# Camera_Board.net
KiCad netlist of a schematic drawn in Altium Designer
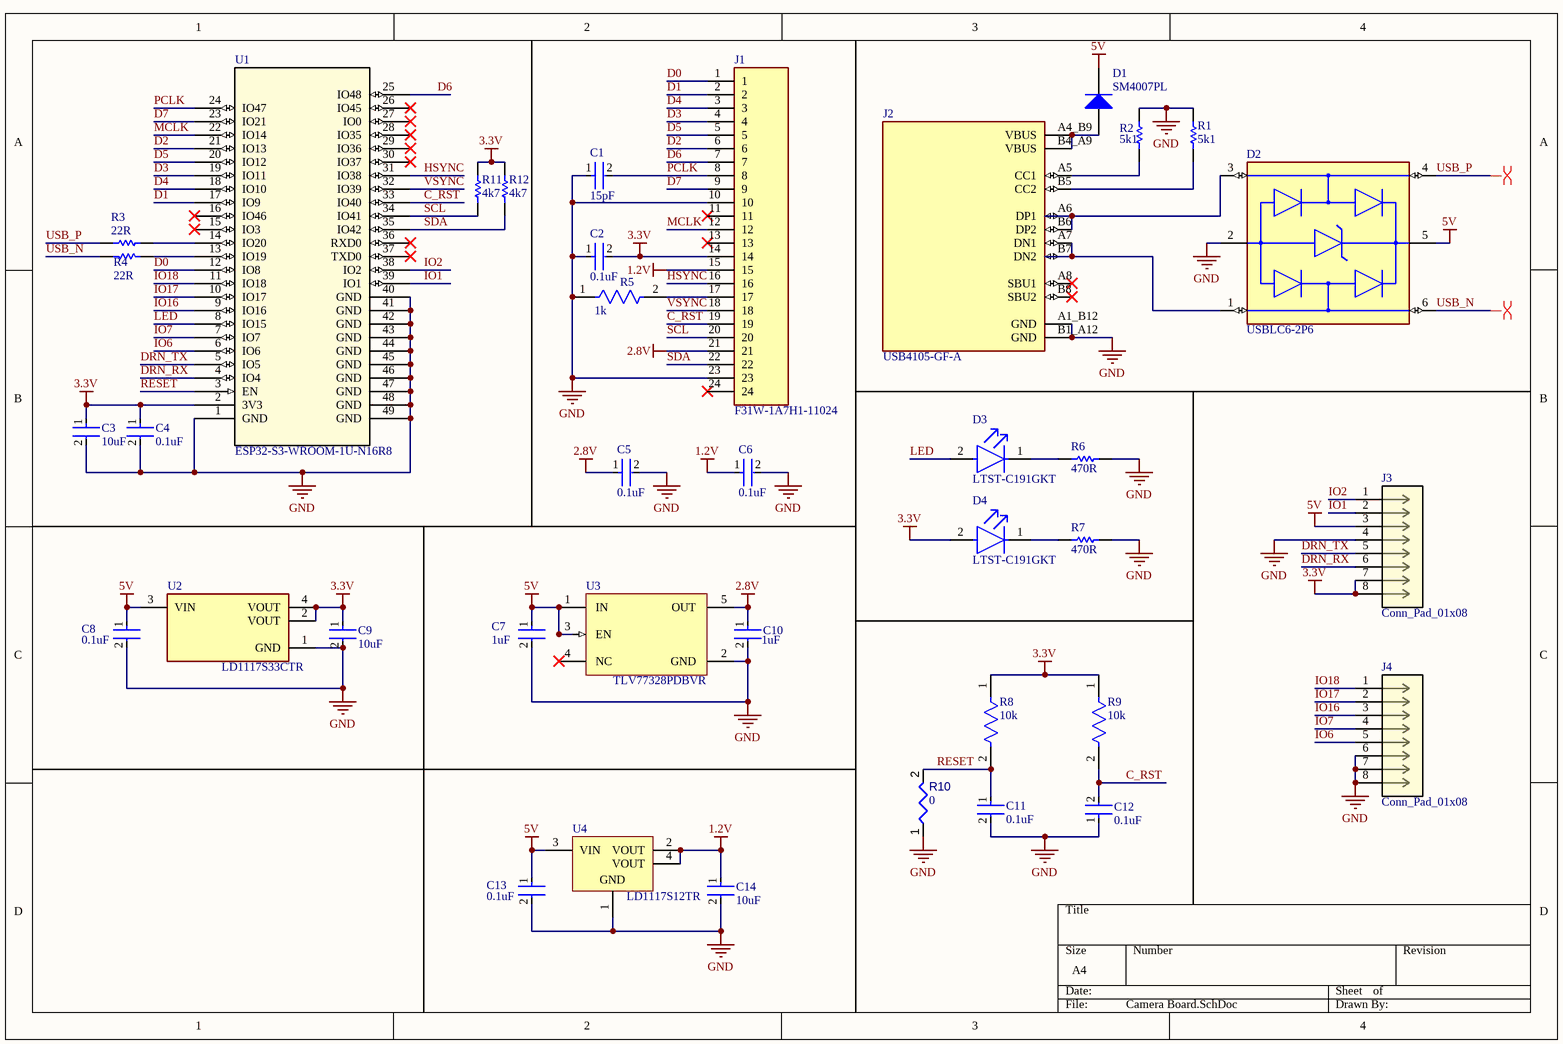
[diagram p0: Camera Board.SchDoc]

(export (version "E")
  (design (tool "Eeschema 10.0.6"))
  (components
    (comp (ref "C1")
      (value "15pF")
      (footprint "FP-CC0402-0_55-IPC_B")
      (description "CAP CER 15PF 50V C0G/NPO 0402")
      (fields (field (name "VOLTAGE") "50V") (field (name "TOLERANCE") "5%"))
      (libsource (lib "Altium Content Vault") (part "b4654b650e69147ec39a6b967a45e02"))
    )
    (comp (ref "C2")
      (value "0.1uF")
      (footprint "FP-GRM155-0_05-IPC_B")
      (description "Chip Multilayer Ceramic Capacitors for General Purpose, 0402, 0.10uF, X7R, 15%, 10%, 50V")
      (fields (field (name "VOLTAGE") "50V") (field (name "TOLERANCE") "10%"))
      (libsource (lib "Altium Content Vault") (part "02cd4be3c70576c341d710602a673aa"))
    )
    (comp (ref "C3")
      (value "10uF")
      (footprint "FP-GRM18-0_15-MFG")
      (description "CAP CER 10UF 10V X5R 0603")
      (fields
        (field (name "OCTOPART") "https://octopart.com/grm188r61a106ke69d-murata-22851381")
        (field (name "MANUFACTURER PART NUMBER") "GRM188R61A106KE69D")
      )
      (libsource (lib "Altium Content Vault") (part "11868f565c42a9108669ba33697ecf6"))
    )
    (comp (ref "C4")
      (value "0.1uF")
      (footprint "FP-CC0603-DA-MFG")
      (description "CAP CER 0.1UF 50V X7R 0603")
      (fields (field (name "MANUFACTURER") "YAGEO") (field (name "VOLTAGE") "50 V"))
      (libsource (lib "Altium Content Vault") (part "11868f565c42a9108669ba33697ecf6"))
    )
    (comp (ref "C5")
      (value "0.1uF")
      (footprint "FP-GRM155-0_05-IPC_B")
      (description "Chip Multilayer Ceramic Capacitors for General Purpose, 0402, 0.10uF, X7R, 15%, 10%, 50V")
      (fields (field (name "VOLTAGE") "50V") (field (name "TOLERANCE") "10%"))
      (libsource (lib "Altium Content Vault") (part "02cd4be3c70576c341d710602a673aa"))
    )
    (comp (ref "C6")
      (value "0.1uF")
      (footprint "FP-GRM155-0_05-IPC_B")
      (description "Chip Multilayer Ceramic Capacitors for General Purpose, 0402, 0.10uF, X7R, 15%, 10%, 50V")
      (fields (field (name "VOLTAGE") "50V") (field (name "TOLERANCE") "10%"))
      (libsource (lib "Altium Content Vault") (part "02cd4be3c70576c341d710602a673aa"))
    )
    (comp (ref "C7")
      (value "1uF")
      (footprint "FP-CC0603-DB-MFG")
      (description "CAP CER 1UF 50V X7R 0603")
      (fields (field (name "TOLERANCE") "10%"))
      (libsource (lib "Altium Content Vault") (part "11868f565c42a9108669ba33697ecf6"))
    )
    (comp (ref "C8")
      (value "0.1uF")
      (footprint "FP-CC0603-DA-MFG")
      (description "CAP CER 0.1UF 50V X7R 0603")
      (fields (field (name "MANUFACTURER") "YAGEO") (field (name "VOLTAGE") "50 V"))
      (libsource (lib "Altium Content Vault") (part "11868f565c42a9108669ba33697ecf6"))
    )
    (comp (ref "C9")
      (value "10uF")
      (footprint "FP-GRM18-0_15-MFG")
      (description "CAP CER 10UF 10V X5R 0603")
      (fields
        (field (name "OCTOPART") "https://octopart.com/grm188r61a106ke69d-murata-22851381")
        (field (name "MANUFACTURER PART NUMBER") "GRM188R61A106KE69D")
      )
      (libsource (lib "Altium Content Vault") (part "11868f565c42a9108669ba33697ecf6"))
    )
    (comp (ref "C10")
      (value "1uF")
      (footprint "FP-CC0603-DB-MFG")
      (description "CAP CER 1UF 50V X7R 0603")
      (fields (field (name "TOLERANCE") "10%"))
      (libsource (lib "Altium Content Vault") (part "11868f565c42a9108669ba33697ecf6"))
    )
    (comp (ref "C11")
      (value "0.1uF")
      (footprint "FP-CC0603-DA-MFG")
      (description "CAP CER 0.1UF 50V X7R 0603")
      (fields (field (name "MANUFACTURER") "YAGEO") (field (name "VOLTAGE") "50 V"))
      (libsource (lib "Altium Content Vault") (part "11868f565c42a9108669ba33697ecf6"))
    )
    (comp (ref "C12")
      (value "0.1uF")
      (footprint "FP-GRM155-0_05-IPC_B")
      (description "Chip Multilayer Ceramic Capacitors for General Purpose, 0402, 0.10uF, X7R, 15%, 10%, 50V")
      (fields (field (name "VOLTAGE") "50V") (field (name "TOLERANCE") "10%"))
      (libsource (lib "Altium Content Vault") (part "02cd4be3c70576c341d710602a673aa"))
    )
    (comp (ref "C13")
      (value "0.1uF")
      (footprint "FP-CC0603-DA-MFG")
      (description "CAP CER 0.1UF 50V X7R 0603")
      (fields (field (name "MANUFACTURER") "YAGEO") (field (name "VOLTAGE") "50 V"))
      (libsource (lib "Altium Content Vault") (part "11868f565c42a9108669ba33697ecf6"))
    )
    (comp (ref "C14")
      (value "10uF")
      (footprint "FP-GRM18-0_15-MFG")
      (description "CAP CER 10UF 10V X5R 0603")
      (fields
        (field (name "OCTOPART") "https://octopart.com/grm188r61a106ke69d-murata-22851381")
        (field (name "MANUFACTURER PART NUMBER") "GRM188R61A106KE69D")
      )
      (libsource (lib "Altium Content Vault") (part "11868f565c42a9108669ba33697ecf6"))
    )
    (comp (ref "D1")
      (value "SM4007PL")
      (footprint "MCC-SOD-123FL_V")
      (description "Silion Rectifier, 1 A, 1000 V, -65 to 175 degC, 2-Pin SMD, RoHS, Tape and Reel")
      (fields (field (name "MANUFACTURER") "Micro Commercial Components"))
      (libsource (lib "Altium Content Vault") (part "D-AK-2"))
    )
    (comp (ref "D2")
      (value "USBLC6-2P6")
      (footprint "FP-SOT-666-MFG")
      (description "TVS DIODE 5.25V 17V SOT666")
      (libsource (lib "Altium Content Vault") (part "c871e55f7e3243d341edbd671b98d92"))
    )
    (comp (ref "D3")
      (value "LTST-C191GKT")
      (footprint "FP-LTST-C191GKT-MFG")
      (description "LED GREEN CLEAR CHIP SMD")
      (libsource (lib "Altium Content Vault") (part "8706943c75ba83719d021d2fdc84c58"))
    )
    (comp (ref "D4")
      (value "LTST-C191GKT")
      (footprint "FP-LTST-C191GKT-MFG")
      (description "LED GREEN CLEAR CHIP SMD")
      (libsource (lib "Altium Content Vault") (part "8706943c75ba83719d021d2fdc84c58"))
    )
    (comp (ref "J1")
      (value "F31W-1A7H1-11024")
      (footprint "AMPHENOL_F31W-1A7H1-11024")
      (fields (field (name "MF") "Amphenol ICC / Aorora"))
      (libsource (lib "Adam Turaj") (part "F31W-1A7H1-11024"))
    )
    (comp (ref "J2")
      (value "USB4105-GF-A")
      (footprint "GCT_USB4105-GF-A")
      (fields (field (name "MF") "{'manufacturer': u'GCT'}"))
      (libsource (lib "Adam Turaj") (part "USB4105-GF-A"))
    )
    (comp (ref "J3")
      (value "Conn_Pad_01x08")
      (footprint "CONN_SM08B-GHS-TB_JST")
      (description "Description")
      (fields (field (name "COPYRIGHT") "Copyright (C) 2026 Ultra Librarian. All rights reserved."))
      (libsource (lib "Adam Turaj") (part "SM08B-GHS-TB"))
    )
    (comp (ref "J4")
      (value "Conn_Pad_01x08")
      (footprint "CONN_SM08B-GHS-TB_JST")
      (description "Description")
      (fields (field (name "COPYRIGHT") "Copyright (C) 2026 Ultra Librarian. All rights reserved."))
      (libsource (lib "Adam Turaj") (part "SM08B-GHS-TB"))
    )
    (comp (ref "R1")
      (value "5k1")
      (footprint "RESC1608X55X25ML10T15")
      (fields (field (name "MANUFACTURER") "Yageo") (field (name "PART NUMBER") "RC0603FR-075K1L"))
      (libsource (lib "Altium Content Vault") (part "RES"))
    )
    (comp (ref "R2")
      (value "5k1")
      (footprint "RESC1608X55X25ML10T15")
      (fields (field (name "MANUFACTURER") "Yageo") (field (name "PART NUMBER") "RC0603FR-075K1L"))
      (libsource (lib "Altium Content Vault") (part "RES"))
    )
    (comp (ref "R3")
      (value "22R")
      (footprint "RESC1608X55X25NL10T15")
      (description "Chip Resistor, 22 Ohm, +/- 1%, 0.1 W, -55 to 155 degC, 0603 (1608 Metric), RoHS, Tape and Reel")
      (libsource (lib "Altium Content Vault") (part "RES-2"))
    )
    (comp (ref "R4")
      (value "22R")
      (footprint "RESC1608X55X25NL10T15")
      (description "Chip Resistor, 22 Ohm, +/- 1%, 0.1 W, -55 to 155 degC, 0603 (1608 Metric), RoHS, Tape and Reel")
      (libsource (lib "Altium Content Vault") (part "RES-2"))
    )
    (comp (ref "R5")
      (value "1k")
      (footprint "FP-RC0603-0_55-IPC_C")
      (description "RES 1K OHM 1% 1/10W 0603")
      (fields (field (name "TOLERANCE") "1%"))
      (libsource (lib "Altium Content Vault") (part "1029c3af85768c4190bb7ad29bc67b5"))
    )
    (comp (ref "R6")
      (value "470R")
      (footprint "RESC1608X55X25LL10T15")
      (libsource (lib "Altium Content Vault") (part "RES-2"))
    )
    (comp (ref "R7")
      (value "470R")
      (footprint "RESC1608X55X25LL10T15")
      (libsource (lib "Altium Content Vault") (part "RES-2"))
    )
    (comp (ref "R8")
      (value "10k")
      (footprint "FP-RC0603-0_55-IPC_C")
      (description "RES 10K OHM 1% 1/10W 0603")
      (fields (field (name "TOLERANCE") "1%"))
      (libsource (lib "Altium Content Vault") (part "1029c3af85768c4190bb7ad29bc67b5"))
    )
    (comp (ref "R9")
      (value "10k")
      (footprint "FP-RC0603-0_55-IPC_C")
      (description "RES 10K OHM 1% 1/10W 0603")
      (fields (field (name "TOLERANCE") "1%"))
      (libsource (lib "Altium Content Vault") (part "1029c3af85768c4190bb7ad29bc67b5"))
    )
    (comp (ref "R10")
      (value "0")
      (footprint "RESC0603(1608)_L")
      (description "Jumper 0603")
      (libsource (lib "UWFE_2025_designs") (part "RES-2"))
    )
    (comp (ref "R11")
      (value "4k7")
      (footprint "RESC1608X55X25LL10T15")
      (description "Chip Resistor, 4.7 KOhm, +/- 1%, 0.1 W, -55 to 155 degC, 0603 (1608 Metric), RoHS, Tape and Reel")
      (fields (field (name "MANUFACTURER") "Yageo") (field (name "TOLERANCE") "1%"))
      (libsource (lib "Altium Content Vault") (part "RES-2"))
    )
    (comp (ref "R12")
      (value "4k7")
      (footprint "RESC1608X55X25LL10T15")
      (description "Chip Resistor, 4.7 KOhm, +/- 1%, 0.1 W, -55 to 155 degC, 0603 (1608 Metric), RoHS, Tape and Reel")
      (fields (field (name "MANUFACTURER") "Yageo") (field (name "TOLERANCE") "1%"))
      (libsource (lib "Altium Content Vault") (part "RES-2"))
    )
    (comp (ref "U1")
      (value "ESP32-S3-WROOM-1U-N16R8")
      (footprint "ESP32-S3-WROOM-1U_EXP")
      (description "Description")
      (fields (field (name "COPYRIGHT") "Copyright (C) 2025 Ultra Librarian. All rights reserved."))
      (libsource (lib "UWFE_2025_designs") (part "ESP32-S3-WROOM-1U-N16R8"))
    )
    (comp (ref "U2")
      (value "LD1117S33CTR")
      (footprint "FP-SOT-223-0046067_14-MFG")
      (description "IC REG LINEAR 3.3V 800MA SOT223")
      (libsource (lib "Altium Content Vault") (part "7818869c5c16ceab15634627166a29d"))
    )
    (comp (ref "U3")
      (value "TLV77328PDBVR")
      (footprint "DBV0005A_MFG")
      (description "300-mA high-PSRR low-IQ low-dropout regulator with enable 5-SOT-23 -40 to 85")
      (libsource (lib "Altium Content Vault") (part "e913c5229f21c84fcd86506975bf48d"))
    )
    (comp (ref "U4")
      (value "LD1117S12TR")
      (footprint "SOT-223_M")
      (description "Fixed Low Drop Positive Voltage Regulator, 1.2V, 4-Pin SOT-223, Tape and Reel")
      (libsource (lib "Altium Content Vault") (part "PM-REG-LD1117-SOT4"))
    )
  )
  (nets
    (net (code "1") (name "/C_RST") (class "Default")
      (node (ref "C12") (pin "2") (pinfunction "2_2") (pintype "passive"))
      (node (ref "J1") (pin "19") (pinfunction "19_19") (pintype "passive"))
      (node (ref "R9") (pin "2") (pinfunction "2_2") (pintype "passive"))
      (node (ref "U1") (pin "33") (pinfunction "IO40_33") (pintype "bidirectional"))
    )
    (net (code "2") (name "/D0") (class "Default")
      (node (ref "J1") (pin "1") (pinfunction "1_1") (pintype "passive"))
      (node (ref "U1") (pin "12") (pinfunction "IO8_12") (pintype "bidirectional"))
    )
    (net (code "3") (name "/D1") (class "Default")
      (node (ref "J1") (pin "2") (pinfunction "2_2") (pintype "passive"))
      (node (ref "U1") (pin "17") (pinfunction "IO9_17") (pintype "bidirectional"))
    )
    (net (code "4") (name "/D2") (class "Default")
      (node (ref "J1") (pin "6") (pinfunction "6_6") (pintype "passive"))
      (node (ref "U1") (pin "21") (pinfunction "IO13_21") (pintype "bidirectional"))
    )
    (net (code "5") (name "/D3") (class "Default")
      (node (ref "J1") (pin "4") (pinfunction "4_4") (pintype "passive"))
      (node (ref "U1") (pin "19") (pinfunction "IO11_19") (pintype "bidirectional"))
    )
    (net (code "6") (name "/D4") (class "Default")
      (node (ref "J1") (pin "3") (pinfunction "3_3") (pintype "passive"))
      (node (ref "U1") (pin "18") (pinfunction "IO10_18") (pintype "bidirectional"))
    )
    (net (code "7") (name "/D5") (class "Default")
      (node (ref "J1") (pin "5") (pinfunction "5_5") (pintype "passive"))
      (node (ref "U1") (pin "20") (pinfunction "IO12_20") (pintype "bidirectional"))
    )
    (net (code "8") (name "/D6") (class "Default")
      (node (ref "J1") (pin "7") (pinfunction "7_7") (pintype "passive"))
      (node (ref "U1") (pin "25") (pinfunction "IO48_25") (pintype "bidirectional"))
    )
    (net (code "9") (name "/D7") (class "Default")
      (node (ref "J1") (pin "9") (pinfunction "9_9") (pintype "passive"))
      (node (ref "U1") (pin "23") (pinfunction "IO21_23") (pintype "bidirectional"))
    )
    (net (code "10") (name "/DRN_RX") (class "Default")
      (node (ref "J3") (pin "6") (pinfunction "6_6") (pintype "passive"))
      (node (ref "U1") (pin "4") (pinfunction "IO4_4") (pintype "bidirectional"))
    )
    (net (code "11") (name "/DRN_TX") (class "Default")
      (node (ref "J3") (pin "5") (pinfunction "5_5") (pintype "passive"))
      (node (ref "U1") (pin "5") (pinfunction "IO5_5") (pintype "bidirectional"))
    )
    (net (code "12") (name "/HSYNC") (class "Default")
      (node (ref "J1") (pin "16") (pinfunction "16_16") (pintype "passive"))
      (node (ref "U1") (pin "31") (pinfunction "IO38_31") (pintype "bidirectional"))
    )
    (net (code "13") (name "/IO1") (class "Default")
      (node (ref "J3") (pin "2") (pinfunction "2_2") (pintype "passive"))
      (node (ref "U1") (pin "39") (pinfunction "IO1_39") (pintype "bidirectional"))
    )
    (net (code "14") (name "/IO2") (class "Default")
      (node (ref "J3") (pin "1") (pinfunction "1_1") (pintype "passive"))
      (node (ref "U1") (pin "38") (pinfunction "IO2_38") (pintype "bidirectional"))
    )
    (net (code "15") (name "/IO6") (class "Default")
      (node (ref "J4") (pin "5") (pinfunction "5_5") (pintype "passive"))
      (node (ref "U1") (pin "6") (pinfunction "IO6_6") (pintype "bidirectional"))
    )
    (net (code "16") (name "/IO7") (class "Default")
      (node (ref "J4") (pin "4") (pinfunction "4_4") (pintype "passive"))
      (node (ref "U1") (pin "7") (pinfunction "IO7_7") (pintype "bidirectional"))
    )
    (net (code "17") (name "/IO16") (class "Default")
      (node (ref "J4") (pin "3") (pinfunction "3_3") (pintype "passive"))
      (node (ref "U1") (pin "9") (pinfunction "IO16_9") (pintype "bidirectional"))
    )
    (net (code "18") (name "/IO17") (class "Default")
      (node (ref "J4") (pin "2") (pinfunction "2_2") (pintype "passive"))
      (node (ref "U1") (pin "10") (pinfunction "IO17_10") (pintype "bidirectional"))
    )
    (net (code "19") (name "/IO18") (class "Default")
      (node (ref "J4") (pin "1") (pinfunction "1_1") (pintype "passive"))
      (node (ref "U1") (pin "11") (pinfunction "IO18_11") (pintype "bidirectional"))
    )
    (net (code "20") (name "/LED") (class "Default")
      (node (ref "D3") (pin "2") (pinfunction "A_2") (pintype "passive"))
      (node (ref "U1") (pin "8") (pinfunction "IO15_8") (pintype "bidirectional"))
    )
    (net (code "21") (name "/MCLK") (class "Default")
      (node (ref "J1") (pin "12") (pinfunction "12_12") (pintype "passive"))
      (node (ref "U1") (pin "22") (pinfunction "IO14_22") (pintype "bidirectional"))
    )
    (net (code "22") (name "/PCLK") (class "Default")
      (node (ref "C1") (pin "2") (pinfunction "2_2") (pintype "passive"))
      (node (ref "J1") (pin "8") (pinfunction "8_8") (pintype "passive"))
      (node (ref "U1") (pin "24") (pinfunction "IO47_24") (pintype "bidirectional"))
    )
    (net (code "23") (name "/RESET") (class "Default")
      (node (ref "C11") (pin "1") (pinfunction "1_1") (pintype "passive"))
      (node (ref "R10") (pin "2") (pinfunction "2_2") (pintype "passive"))
      (node (ref "R8") (pin "2") (pinfunction "2_2") (pintype "passive"))
      (node (ref "U1") (pin "3") (pinfunction "EN_3") (pintype "input"))
    )
    (net (code "24") (name "/SCL") (class "Default")
      (node (ref "J1") (pin "20") (pinfunction "20_20") (pintype "passive"))
      (node (ref "R11") (pin "1") (pinfunction "1_1") (pintype "passive"))
      (node (ref "U1") (pin "34") (pinfunction "IO41_34") (pintype "bidirectional"))
    )
    (net (code "25") (name "/SDA") (class "Default")
      (node (ref "J1") (pin "22") (pinfunction "22_22") (pintype "passive"))
      (node (ref "R12") (pin "1") (pinfunction "1_1") (pintype "passive"))
      (node (ref "U1") (pin "35") (pinfunction "IO42_35") (pintype "bidirectional"))
    )
    (net (code "26") (name "/USB_N") (class "Default")
      (node (ref "D2") (pin "6") (pinfunction "I/O1_6") (pintype "bidirectional"))
      (node (ref "R4") (pin "1") (pinfunction "1_1") (pintype "passive"))
    )
    (net (code "27") (name "/USB_P") (class "Default")
      (node (ref "D2") (pin "4") (pinfunction "I/O2_4") (pintype "bidirectional"))
      (node (ref "R3") (pin "1") (pinfunction "1_1") (pintype "passive"))
    )
    (net (code "28") (name "/VSYNC") (class "Default")
      (node (ref "J1") (pin "18") (pinfunction "18_18") (pintype "passive"))
      (node (ref "U1") (pin "32") (pinfunction "IO39_32") (pintype "bidirectional"))
    )
    (net (code "29") (name "1.2V") (class "Default")
      (node (ref "C14") (pin "1") (pinfunction "1_1") (pintype "passive"))
      (node (ref "C6") (pin "1") (pinfunction "1_1") (pintype "passive"))
      (node (ref "J1") (pin "15") (pinfunction "15_15") (pintype "passive"))
      (node (ref "U4") (pin "2") (pinfunction "VOUT_2") (pintype "power_in"))
      (node (ref "U4") (pin "4") (pinfunction "VOUT_4") (pintype "power_in"))
    )
    (net (code "30") (name "2.8V") (class "Default")
      (node (ref "C10") (pin "1") (pinfunction "1_1") (pintype "passive"))
      (node (ref "C5") (pin "1") (pinfunction "1_1") (pintype "passive"))
      (node (ref "J1") (pin "21") (pinfunction "21_21") (pintype "passive"))
      (node (ref "U3") (pin "5") (pinfunction "OUT_5") (pintype "passive"))
    )
    (net (code "31") (name "3.3V") (class "Default")
      (node (ref "C2") (pin "2") (pinfunction "2_2") (pintype "passive"))
      (node (ref "C3") (pin "1") (pinfunction "1_1") (pintype "passive"))
      (node (ref "C4") (pin "1") (pinfunction "1_1") (pintype "passive"))
      (node (ref "C9") (pin "1") (pinfunction "1_1") (pintype "passive"))
      (node (ref "D4") (pin "2") (pinfunction "A_2") (pintype "passive"))
      (node (ref "J1") (pin "14") (pinfunction "14_14") (pintype "passive"))
      (node (ref "J3") (pin "7") (pinfunction "7_7") (pintype "passive"))
      (node (ref "J3") (pin "8") (pinfunction "8_8") (pintype "passive"))
      (node (ref "R11") (pin "2") (pinfunction "2_2") (pintype "passive"))
      (node (ref "R12") (pin "2") (pinfunction "2_2") (pintype "passive"))
      (node (ref "R8") (pin "1") (pinfunction "1_1") (pintype "passive"))
      (node (ref "R9") (pin "1") (pinfunction "1_1") (pintype "passive"))
      (node (ref "U1") (pin "2") (pinfunction "3V3_2") (pintype "power_in"))
      (node (ref "U2") (pin "2") (pinfunction "VOUT_2") (pintype "power_in"))
      (node (ref "U2") (pin "4") (pinfunction "VOUT_4") (pintype "power_in"))
    )
    (net (code "32") (name "5V") (class "Default")
      (node (ref "C13") (pin "1") (pinfunction "1_1") (pintype "passive"))
      (node (ref "C7") (pin "1") (pinfunction "1_1") (pintype "passive"))
      (node (ref "C8") (pin "1") (pinfunction "1_1") (pintype "passive"))
      (node (ref "D1") (pin "2") (pinfunction "K_2") (pintype "passive"))
      (node (ref "D2") (pin "5") (pinfunction "VBUS_5") (pintype "power_in"))
      (node (ref "J3") (pin "3") (pinfunction "3_3") (pintype "passive"))
      (node (ref "U2") (pin "3") (pinfunction "VIN_3") (pintype "power_in"))
      (node (ref "U3") (pin "1") (pinfunction "IN_1") (pintype "power_in"))
      (node (ref "U3") (pin "3") (pinfunction "EN_3") (pintype "input"))
      (node (ref "U4") (pin "3") (pinfunction "VIN_3") (pintype "power_in"))
    )
    (net (code "33") (name "GND") (class "Default")
      (node (ref "C1") (pin "1") (pinfunction "1_1") (pintype "passive"))
      (node (ref "C10") (pin "2") (pinfunction "2_2") (pintype "passive"))
      (node (ref "C11") (pin "2") (pinfunction "2_2") (pintype "passive"))
      (node (ref "C12") (pin "1") (pinfunction "1_1") (pintype "passive"))
      (node (ref "C13") (pin "2") (pinfunction "2_2") (pintype "passive"))
      (node (ref "C14") (pin "2") (pinfunction "2_2") (pintype "passive"))
      (node (ref "C2") (pin "1") (pinfunction "1_1") (pintype "passive"))
      (node (ref "C3") (pin "2") (pinfunction "2_2") (pintype "passive"))
      (node (ref "C4") (pin "2") (pinfunction "2_2") (pintype "passive"))
      (node (ref "C5") (pin "2") (pinfunction "2_2") (pintype "passive"))
      (node (ref "C6") (pin "2") (pinfunction "2_2") (pintype "passive"))
      (node (ref "C7") (pin "2") (pinfunction "2_2") (pintype "passive"))
      (node (ref "C8") (pin "2") (pinfunction "2_2") (pintype "passive"))
      (node (ref "C9") (pin "2") (pinfunction "2_2") (pintype "passive"))
      (node (ref "D2") (pin "2") (pinfunction "GND_2") (pintype "power_in"))
      (node (ref "J1") (pin "10") (pinfunction "10_10") (pintype "passive"))
      (node (ref "J1") (pin "23") (pinfunction "23_23") (pintype "passive"))
      (node (ref "J2") (pin "A1_B12") (pinfunction "GND_A1_B12") (pintype "power_in"))
      (node (ref "J2") (pin "B1_A12") (pinfunction "GND_B1_A12") (pintype "power_in"))
      (node (ref "J3") (pin "4") (pinfunction "4_4") (pintype "passive"))
      (node (ref "J4") (pin "6") (pinfunction "6_6") (pintype "passive"))
      (node (ref "J4") (pin "7") (pinfunction "7_7") (pintype "passive"))
      (node (ref "J4") (pin "8") (pinfunction "8_8") (pintype "passive"))
      (node (ref "R1") (pin "2") (pinfunction "2_2") (pintype "passive"))
      (node (ref "R10") (pin "1") (pinfunction "1_1") (pintype "passive"))
      (node (ref "R2") (pin "2") (pinfunction "2_2") (pintype "passive"))
      (node (ref "R5") (pin "1") (pinfunction "1_1") (pintype "passive"))
      (node (ref "R6") (pin "2") (pinfunction "2_2") (pintype "passive"))
      (node (ref "R7") (pin "2") (pinfunction "2_2") (pintype "passive"))
      (node (ref "U1") (pin "1") (pinfunction "GND_1") (pintype "power_in"))
      (node (ref "U1") (pin "40") (pinfunction "GND_40") (pintype "power_in"))
      (node (ref "U1") (pin "41") (pinfunction "GND_41") (pintype "power_in"))
      (node (ref "U1") (pin "42") (pinfunction "GND_42") (pintype "power_in"))
      (node (ref "U1") (pin "43") (pinfunction "GND_43") (pintype "power_in"))
      (node (ref "U1") (pin "44") (pinfunction "GND_44") (pintype "power_in"))
      (node (ref "U1") (pin "45") (pinfunction "GND_45") (pintype "power_in"))
      (node (ref "U1") (pin "46") (pinfunction "GND_46") (pintype "power_in"))
      (node (ref "U1") (pin "47") (pinfunction "GND_47") (pintype "power_in"))
      (node (ref "U1") (pin "48") (pinfunction "GND_48") (pintype "power_in"))
      (node (ref "U1") (pin "49") (pinfunction "GND_49") (pintype "power_in"))
      (node (ref "U2") (pin "1") (pinfunction "GND_1") (pintype "power_in"))
      (node (ref "U3") (pin "2") (pinfunction "GND_2") (pintype "power_in"))
      (node (ref "U4") (pin "1") (pinfunction "GND_1") (pintype "power_in"))
    )
    (net (code "34") (name "Net-(D1-A)") (class "Default")
      (node (ref "D1") (pin "1") (pinfunction "A_1") (pintype "passive"))
      (node (ref "J2") (pin "A4_B9") (pinfunction "VBUS_A4_B9") (pintype "power_in"))
      (node (ref "J2") (pin "B4_A9") (pinfunction "VBUS_B4_A9") (pintype "power_in"))
    )
    (net (code "35") (name "Net-(D3-C)") (class "Default")
      (node (ref "D3") (pin "1") (pinfunction "C_1") (pintype "passive"))
      (node (ref "R6") (pin "1") (pinfunction "1_1") (pintype "passive"))
    )
    (net (code "36") (name "Net-(D4-C)") (class "Default")
      (node (ref "D4") (pin "1") (pinfunction "C_1") (pintype "passive"))
      (node (ref "R7") (pin "1") (pinfunction "1_1") (pintype "passive"))
    )
    (net (code "37") (name "Net-(J1-Pad17)") (class "Default")
      (node (ref "J1") (pin "17") (pinfunction "17_17") (pintype "passive"))
      (node (ref "R5") (pin "2") (pinfunction "2_2") (pintype "passive"))
    )
    (net (code "38") (name "Net-(J2-CC1)") (class "Default")
      (node (ref "J2") (pin "A5") (pinfunction "CC1_A5") (pintype "bidirectional"))
      (node (ref "R2") (pin "1") (pinfunction "1_1") (pintype "passive"))
    )
    (net (code "39") (name "Net-(J2-CC2)") (class "Default")
      (node (ref "J2") (pin "B5") (pinfunction "CC2_B5") (pintype "bidirectional"))
      (node (ref "R1") (pin "1") (pinfunction "1_1") (pintype "passive"))
    )
    (net (code "40") (name "Net-(J2-DN1)") (class "Default")
      (node (ref "D2") (pin "1") (pinfunction "I/O1_1") (pintype "bidirectional"))
      (node (ref "J2") (pin "A7") (pinfunction "DN1_A7") (pintype "bidirectional"))
      (node (ref "J2") (pin "B7") (pinfunction "DN2_B7") (pintype "bidirectional"))
    )
    (net (code "41") (name "Net-(J2-DP1)") (class "Default")
      (node (ref "D2") (pin "3") (pinfunction "I/O2_3") (pintype "bidirectional"))
      (node (ref "J2") (pin "A6") (pinfunction "DP1_A6") (pintype "bidirectional"))
      (node (ref "J2") (pin "B6") (pinfunction "DP2_B6") (pintype "bidirectional"))
    )
    (net (code "42") (name "Net-(U1-IO19)") (class "Default")
      (node (ref "R4") (pin "2") (pinfunction "2_2") (pintype "passive"))
      (node (ref "U1") (pin "13") (pinfunction "IO19_13") (pintype "bidirectional"))
    )
    (net (code "43") (name "Net-(U1-IO20)") (class "Default")
      (node (ref "R3") (pin "2") (pinfunction "2_2") (pintype "passive"))
      (node (ref "U1") (pin "14") (pinfunction "IO20_14") (pintype "bidirectional"))
    )
    (net (code "44") (name "unconnected-(J1-Pad11)") (class "Default")
      (node (ref "J1") (pin "11") (pinfunction "11_11") (pintype "passive+no_connect"))
    )
    (net (code "45") (name "unconnected-(J1-Pad13)") (class "Default")
      (node (ref "J1") (pin "13") (pinfunction "13_13") (pintype "passive+no_connect"))
    )
    (net (code "46") (name "unconnected-(J1-Pad24)") (class "Default")
      (node (ref "J1") (pin "24") (pinfunction "24_24") (pintype "passive+no_connect"))
    )
    (net (code "47") (name "unconnected-(J2-SBU1-PadA8)") (class "Default")
      (node (ref "J2") (pin "A8") (pinfunction "SBU1_A8") (pintype "bidirectional+no_connect"))
    )
    (net (code "48") (name "unconnected-(J2-SBU2-PadB8)") (class "Default")
      (node (ref "J2") (pin "B8") (pinfunction "SBU2_B8") (pintype "bidirectional+no_connect"))
    )
    (net (code "49") (name "unconnected-(U1-IO0-Pad27)") (class "Default")
      (node (ref "U1") (pin "27") (pinfunction "IO0_27") (pintype "bidirectional+no_connect"))
    )
    (net (code "50") (name "unconnected-(U1-IO3-Pad15)") (class "Default")
      (node (ref "U1") (pin "15") (pinfunction "IO3_15") (pintype "bidirectional+no_connect"))
    )
    (net (code "51") (name "unconnected-(U1-IO35-Pad28)") (class "Default")
      (node (ref "U1") (pin "28") (pinfunction "IO35_28") (pintype "bidirectional+no_connect"))
    )
    (net (code "52") (name "unconnected-(U1-IO36-Pad29)") (class "Default")
      (node (ref "U1") (pin "29") (pinfunction "IO36_29") (pintype "bidirectional+no_connect"))
    )
    (net (code "53") (name "unconnected-(U1-IO37-Pad30)") (class "Default")
      (node (ref "U1") (pin "30") (pinfunction "IO37_30") (pintype "bidirectional+no_connect"))
    )
    (net (code "54") (name "unconnected-(U1-IO45-Pad26)") (class "Default")
      (node (ref "U1") (pin "26") (pinfunction "IO45_26") (pintype "bidirectional+no_connect"))
    )
    (net (code "55") (name "unconnected-(U1-IO46-Pad16)") (class "Default")
      (node (ref "U1") (pin "16") (pinfunction "IO46_16") (pintype "bidirectional+no_connect"))
    )
    (net (code "56") (name "unconnected-(U1-RXD0-Pad36)") (class "Default")
      (node (ref "U1") (pin "36") (pinfunction "RXD0_36") (pintype "bidirectional+no_connect"))
    )
    (net (code "57") (name "unconnected-(U1-TXD0-Pad37)") (class "Default")
      (node (ref "U1") (pin "37") (pinfunction "TXD0_37") (pintype "bidirectional+no_connect"))
    )
    (net (code "58") (name "unconnected-(U3-NC-Pad4)") (class "Default")
      (node (ref "U3") (pin "4") (pinfunction "NC_4") (pintype "passive+no_connect"))
    )
  )
)
